# STM32.net
KiCad netlist of a schematic drawn in Altium Designer
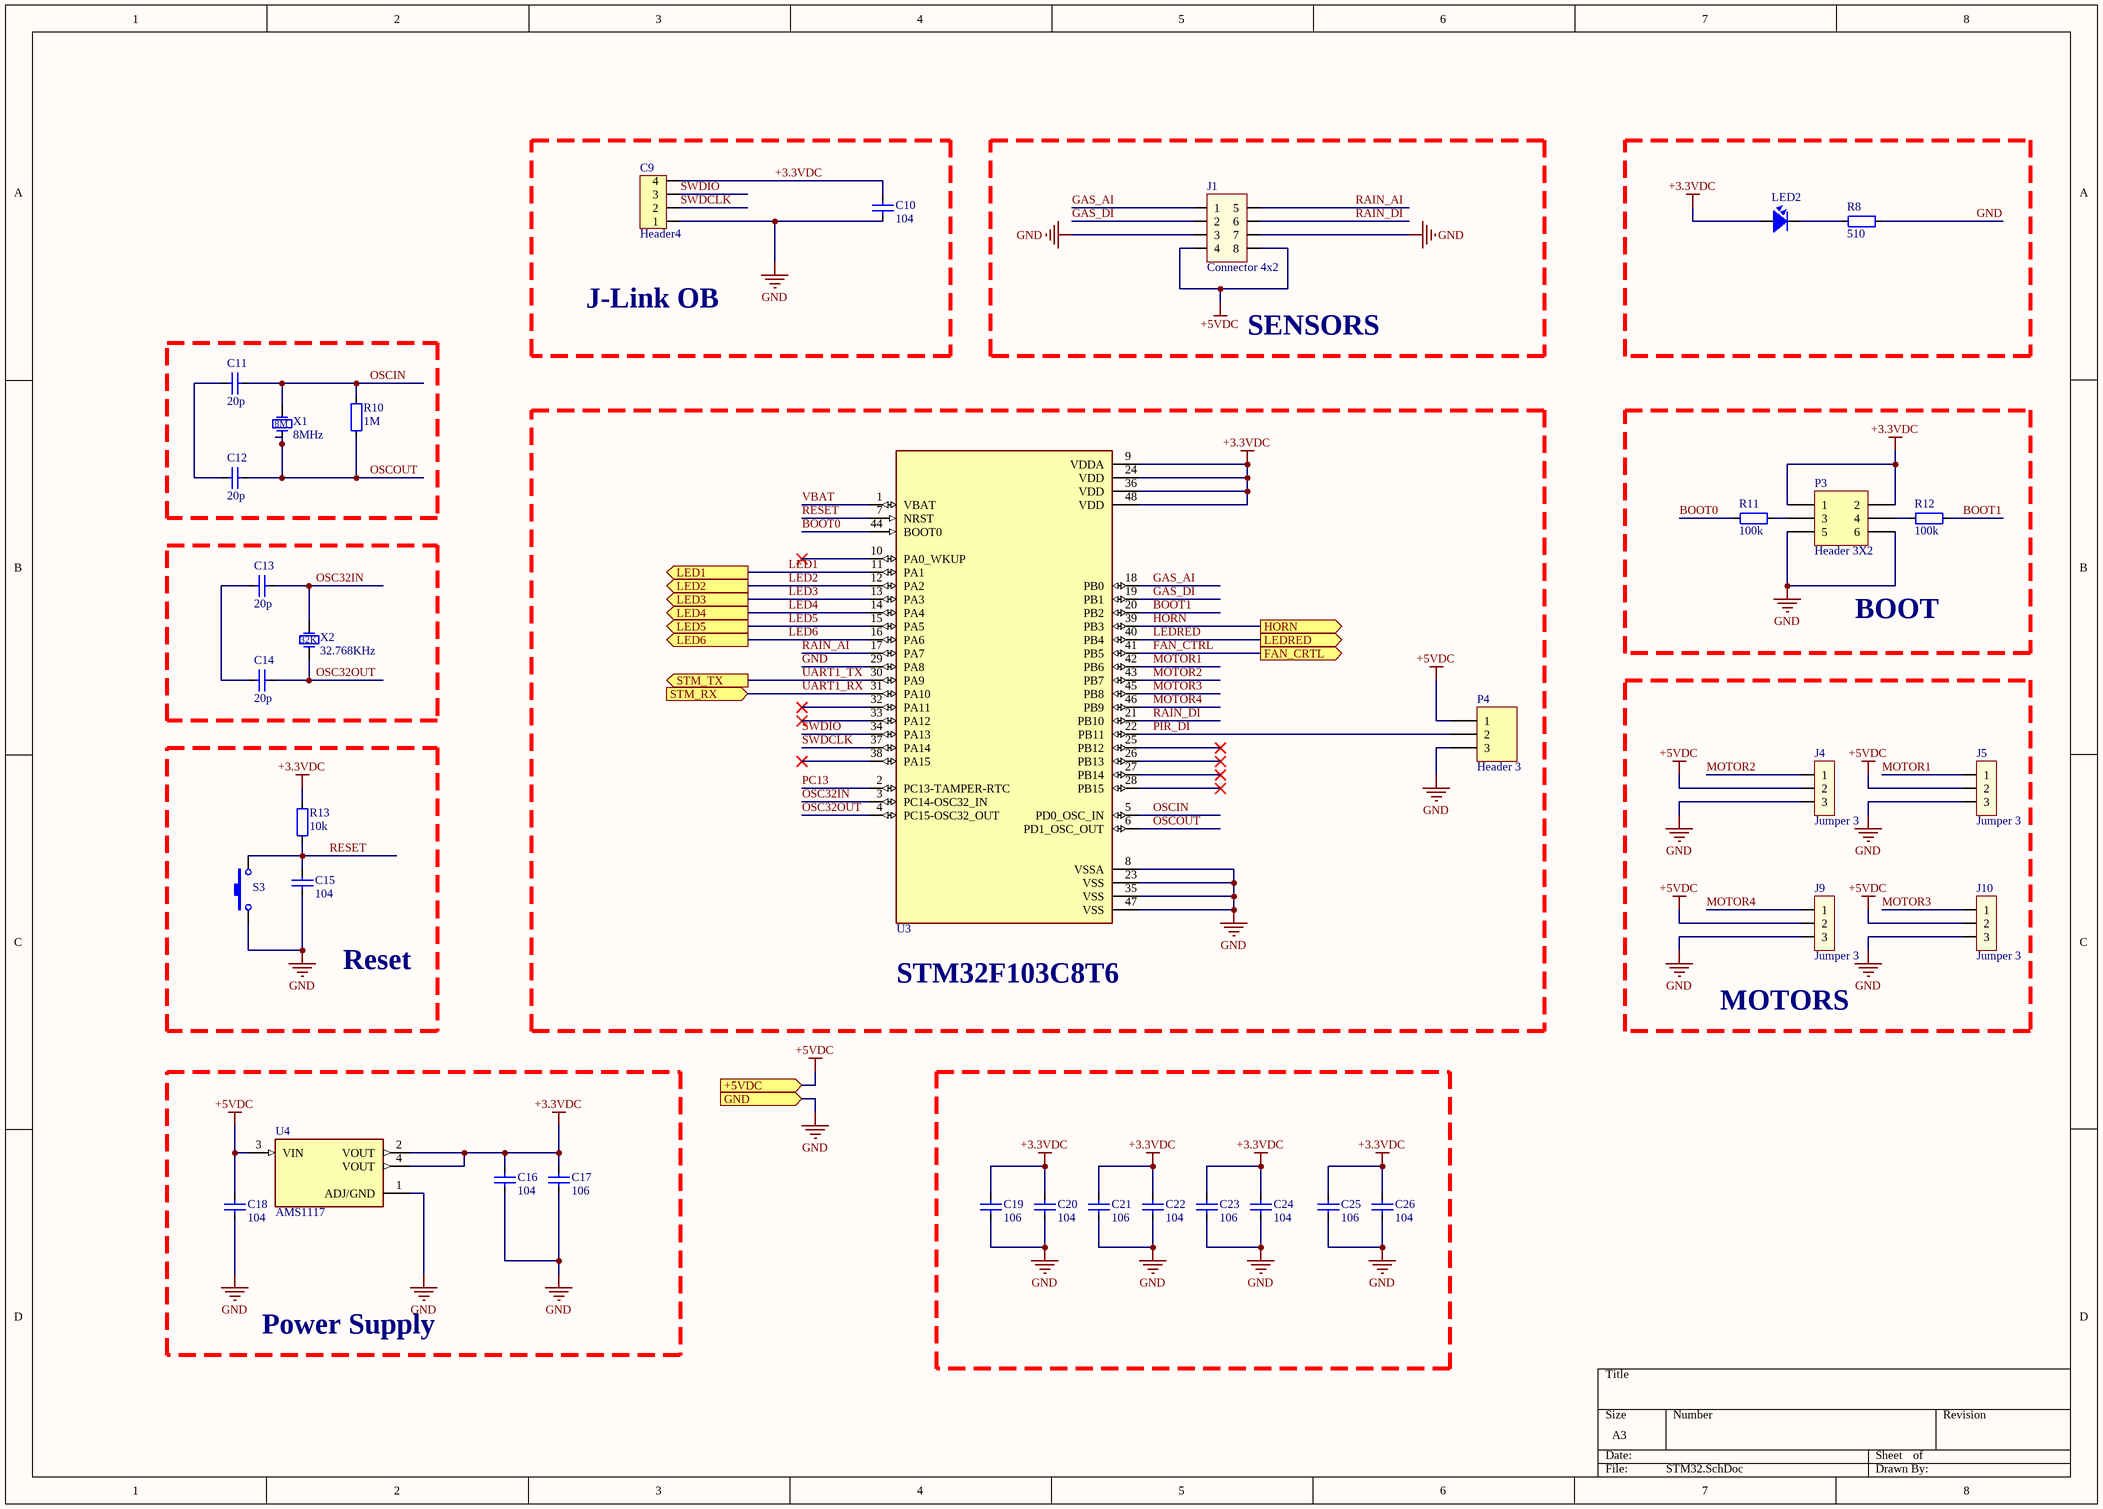
[diagram p0: STM32.SchDoc]

(export (version "E")
  (design (tool "Eeschema 10.0.6"))
  (components
    (comp (ref "C9")
      (value "Header4")
      (footprint "Header4")
      (description "Header IDC, 4 x 1 Pin Vertical 2.54mm Pitch (Non-Boxed, Male)")
      (fields
        (field (name "MANUFACTURER") "Würth Elektronik eiSos GmbH")
        (field (name "PARTNO") "613002143121")
        (field (name "CREATED BY") "Karrer Zheng")
      )
      (libsource (lib "My Library") (part "Header4"))
    )
    (comp (ref "C10")
      (value "104")
      (footprint "CAP_0805")
      (description "Capacitor")
      (fields (field (name "PUBLISHER") "Altium Limited"))
      (libsource (lib "My Library") (part "CapSMD"))
    )
    (comp (ref "C11")
      (value "20p")
      (footprint "CAP_0805")
      (description "Capacitor")
      (fields (field (name "PUBLISHER") "Altium Limited"))
      (libsource (lib "My Library") (part "CapSMD"))
    )
    (comp (ref "C12")
      (value "20p")
      (footprint "CAP_0805")
      (description "Capacitor")
      (fields (field (name "PUBLISHER") "Altium Limited"))
      (libsource (lib "My Library") (part "CapSMD"))
    )
    (comp (ref "C13")
      (value "20p")
      (footprint "CAP_0805")
      (description "Capacitor")
      (fields (field (name "PUBLISHER") "Altium Limited"))
      (libsource (lib "My Library") (part "CapSMD"))
    )
    (comp (ref "C14")
      (value "20p")
      (footprint "CAP_0805")
      (description "Capacitor")
      (fields (field (name "PUBLISHER") "Altium Limited"))
      (libsource (lib "My Library") (part "CapSMD"))
    )
    (comp (ref "C15")
      (value "104")
      (footprint "CAP_0805")
      (description "Capacitor")
      (fields (field (name "PUBLISHER") "Altium Limited"))
      (libsource (lib "My Library") (part "CapSMD"))
    )
    (comp (ref "C16")
      (value "104")
      (footprint "CAP_0805")
      (description "Capacitor")
      (fields (field (name "PUBLISHER") "Altium Limited"))
      (libsource (lib "My Library") (part "CapSMD"))
    )
    (comp (ref "C17")
      (value "106")
      (footprint "CAP_0805")
      (description "Capacitor")
      (fields (field (name "PUBLISHER") "Altium Limited"))
      (libsource (lib "My Library") (part "CapSMD"))
    )
    (comp (ref "C18")
      (value "104")
      (footprint "CAP_0805")
      (description "Capacitor")
      (fields (field (name "PUBLISHER") "Altium Limited"))
      (libsource (lib "My Library") (part "CapSMD"))
    )
    (comp (ref "C19")
      (value "106")
      (footprint "CAP_0805")
      (description "Capacitor")
      (fields (field (name "PUBLISHER") "Altium Limited"))
      (libsource (lib "My Library") (part "CapSMD"))
    )
    (comp (ref "C20")
      (value "104")
      (footprint "CAP_0805")
      (description "Capacitor")
      (fields (field (name "PUBLISHER") "Altium Limited"))
      (libsource (lib "My Library") (part "CapSMD"))
    )
    (comp (ref "C21")
      (value "106")
      (footprint "CAP_0805")
      (description "Capacitor")
      (fields (field (name "PUBLISHER") "Altium Limited"))
      (libsource (lib "My Library") (part "CapSMD"))
    )
    (comp (ref "C22")
      (value "104")
      (footprint "CAP_0805")
      (description "Capacitor")
      (fields (field (name "PUBLISHER") "Altium Limited"))
      (libsource (lib "My Library") (part "CapSMD"))
    )
    (comp (ref "C23")
      (value "106")
      (footprint "CAP_0805")
      (description "Capacitor")
      (fields (field (name "PUBLISHER") "Altium Limited"))
      (libsource (lib "My Library") (part "CapSMD"))
    )
    (comp (ref "C24")
      (value "104")
      (footprint "CAP_0805")
      (description "Capacitor")
      (fields (field (name "PUBLISHER") "Altium Limited"))
      (libsource (lib "My Library") (part "CapSMD"))
    )
    (comp (ref "C25")
      (value "106")
      (footprint "CAP_0805")
      (description "Capacitor")
      (fields (field (name "PUBLISHER") "Altium Limited"))
      (libsource (lib "My Library") (part "CapSMD"))
    )
    (comp (ref "C26")
      (value "104")
      (footprint "CAP_0805")
      (description "Capacitor")
      (fields (field (name "PUBLISHER") "Altium Limited"))
      (libsource (lib "My Library") (part "CapSMD"))
    )
    (comp (ref "J1")
      (value "Connector 4x2")
      (footprint "JP4x2")
      (libsource (lib "My Library") (part "JP4x2"))
    )
    (comp (ref "J4") (value "Jumper 3") (footprint "JP3") (libsource (lib "My Library") (part "JP3")))
    (comp (ref "J5") (value "Jumper 3") (footprint "JP3") (libsource (lib "My Library") (part "JP3")))
    (comp (ref "J9") (value "Jumper 3") (footprint "JP3") (libsource (lib "My Library") (part "JP3")))
    (comp (ref "J10") (value "Jumper 3") (footprint "JP3") (libsource (lib "My Library") (part "JP3")))
    (comp (ref "LED2")
      (value "LED")
      (footprint "LED-0805-Red")
      (description "LED Single colour Green and Red")
      (libsource (lib "My Library") (part "LED"))
    )
    (comp (ref "P3")
      (value "Header 3X2")
      (footprint "HDR2X3")
      (description "Header, 3-Pin, Dual row")
      (fields (field (name "PUBLISHER") "Altium Limited"))
      (libsource (lib "My Library") (part "Header 3X2"))
    )
    (comp (ref "P4")
      (value "Header 3")
      (footprint "HDR1X3")
      (description "Header, 3-Pin")
      (fields (field (name "PUBLISHER") "Altium Limited"))
      (libsource (lib "My Library") (part "Header 3"))
    )
    (comp (ref "R8")
      (value "510")
      (footprint "RES-SMD-0805")
      (description "Resistor")
      (fields
        (field (name "MANUFACTURER") "Generic Components")
        (field (name "PUBLISHER") "Altium Hobart Technology Centre")
      )
      (libsource (lib "My Library") (part "Resistor - SMD"))
    )
    (comp (ref "R10")
      (value "1M")
      (footprint "RES-SMD-0805")
      (description "Resistor")
      (fields
        (field (name "MANUFACTURER") "Generic Components")
        (field (name "PUBLISHER") "Altium Hobart Technology Centre")
      )
      (libsource (lib "My Library") (part "Resistor - SMD"))
    )
    (comp (ref "R11")
      (value "100k")
      (footprint "RES-SMD-0805")
      (description "Resistor")
      (fields
        (field (name "MANUFACTURER") "Generic Components")
        (field (name "PUBLISHER") "Altium Hobart Technology Centre")
      )
      (libsource (lib "My Library") (part "Resistor - SMD"))
    )
    (comp (ref "R12")
      (value "100k")
      (footprint "RES-SMD-0805")
      (description "Resistor")
      (fields
        (field (name "MANUFACTURER") "Generic Components")
        (field (name "PUBLISHER") "Altium Hobart Technology Centre")
      )
      (libsource (lib "My Library") (part "Resistor - SMD"))
    )
    (comp (ref "R13")
      (value "10k")
      (footprint "RES-SMD-0805")
      (description "Resistor")
      (fields
        (field (name "MANUFACTURER") "Generic Components")
        (field (name "PUBLISHER") "Altium Hobart Technology Centre")
      )
      (libsource (lib "My Library") (part "Resistor - SMD"))
    )
    (comp (ref "S3")
      (value "SW-SMD")
      (footprint "SW-SMD")
      (description "Switch")
      (fields (field (name "PUBLISHER") "Altium Limited"))
      (libsource (lib "My Library") (part "SW-SMD"))
    )
    (comp (ref "U3")
      (value "STM32")
      (footprint "LQFP 48")
      (description "STM32 ARM-based 32-bit MCU with 64 Kbytes Flash, 64-pin LQFP, Industrial Temperature")
      (libsource (lib "My Library") (part "STM32F103C8T6"))
    )
    (comp (ref "U4")
      (value "AMS1117")
      (footprint "SOT229P700X180-4N")
      (description "1A LOW DROPOUT VOLTAGE REGULATOR SOT-223")
      (fields (field (name "MF") "Advanced Monolithic Systems"))
      (libsource (lib "AMS1117") (part "AMS1117"))
    )
    (comp (ref "X1")
      (value "8MHz")
      (footprint "CRYSTAL_ABM3 5x3.2mm")
      (description "CRYSTAL 8.0000MHZ 18pF SMD")
      (fields (field (name "MPN") "ABM3-8.000MHZ-D2Y-T"))
      (libsource (lib "BYTECH_HW_LIB_2019") (part "ABM3-8.000MHZ-D2Y-T"))
    )
    (comp (ref "X2")
      (value "32.768KHz")
      (footprint "Crystal_ABS07_SMD-3.2x1.5MM")
      (description "CRYSTAL 32.7680KHZ 12.5pF SMD")
      (fields (field (name "MPN") "ABS07-32.768KHZ-T"))
      (libsource (lib "BYTECH_HW_LIB_2019") (part "ABS07-32.768KHZ-T"))
    )
  )
  (nets
    (net (code "1") (name "+3.3VDC") (class "Default")
      (node (ref "C10") (pin "2") (pinfunction "2_2") (pintype "passive"))
      (node (ref "C16") (pin "2") (pinfunction "2_2") (pintype "passive"))
      (node (ref "C17") (pin "2") (pinfunction "2_2") (pintype "passive"))
      (node (ref "C19") (pin "2") (pinfunction "2_2") (pintype "passive"))
      (node (ref "C20") (pin "2") (pinfunction "2_2") (pintype "passive"))
      (node (ref "C21") (pin "2") (pinfunction "2_2") (pintype "passive"))
      (node (ref "C22") (pin "2") (pinfunction "2_2") (pintype "passive"))
      (node (ref "C23") (pin "2") (pinfunction "2_2") (pintype "passive"))
      (node (ref "C24") (pin "2") (pinfunction "2_2") (pintype "passive"))
      (node (ref "C25") (pin "2") (pinfunction "2_2") (pintype "passive"))
      (node (ref "C26") (pin "2") (pinfunction "2_2") (pintype "passive"))
      (node (ref "C9") (pin "4") (pinfunction "4_4") (pintype "passive"))
      (node (ref "LED2") (pin "1") (pinfunction "1_1") (pintype "passive"))
      (node (ref "P3") (pin "1") (pinfunction "1_1") (pintype "passive"))
      (node (ref "P3") (pin "2") (pinfunction "2_2") (pintype "passive"))
      (node (ref "R13") (pin "2") (pinfunction "2_2") (pintype "passive"))
      (node (ref "U3") (pin "24") (pinfunction "VDD_24") (pintype "power_in"))
      (node (ref "U3") (pin "36") (pinfunction "VDD_36") (pintype "power_in"))
      (node (ref "U3") (pin "48") (pinfunction "VDD_48") (pintype "power_in"))
      (node (ref "U3") (pin "9") (pinfunction "VDDA_9") (pintype "power_in"))
      (node (ref "U4") (pin "2") (pinfunction "VOUT_2") (pintype "output"))
      (node (ref "U4") (pin "4") (pinfunction "VOUT_4") (pintype "output"))
    )
    (net (code "2") (name "+5VDC") (class "Default")
      (node (ref "C18") (pin "2") (pinfunction "2_2") (pintype "passive"))
      (node (ref "J1") (pin "4") (pinfunction "4_4") (pintype "passive"))
      (node (ref "J1") (pin "8") (pinfunction "8_8") (pintype "passive"))
      (node (ref "J10") (pin "2") (pinfunction "2_2") (pintype "passive"))
      (node (ref "J4") (pin "2") (pinfunction "2_2") (pintype "passive"))
      (node (ref "J5") (pin "2") (pinfunction "2_2") (pintype "passive"))
      (node (ref "J9") (pin "2") (pinfunction "2_2") (pintype "passive"))
      (node (ref "P4") (pin "1") (pinfunction "1_1") (pintype "passive"))
      (node (ref "U4") (pin "3") (pinfunction "VIN_3") (pintype "input"))
    )
    (net (code "3") (name "/BOOT0") (class "Default")
      (node (ref "R11") (pin "2") (pinfunction "2_2") (pintype "passive"))
      (node (ref "U3") (pin "44") (pinfunction "BOOT0_44") (pintype "input"))
    )
    (net (code "4") (name "/BOOT1") (class "Default")
      (node (ref "R12") (pin "1") (pinfunction "1_1") (pintype "passive"))
      (node (ref "U3") (pin "20") (pinfunction "PB2_20") (pintype "bidirectional"))
    )
    (net (code "5") (name "/FAN_CTRL") (class "Default")
      (node (ref "U3") (pin "41") (pinfunction "PB5_41") (pintype "bidirectional"))
    )
    (net (code "6") (name "/GAS_AI") (class "Default")
      (node (ref "J1") (pin "1") (pinfunction "1_1") (pintype "passive"))
      (node (ref "U3") (pin "18") (pinfunction "PB0_18") (pintype "bidirectional"))
    )
    (net (code "7") (name "/GAS_DI") (class "Default")
      (node (ref "J1") (pin "2") (pinfunction "2_2") (pintype "passive"))
      (node (ref "U3") (pin "19") (pinfunction "PB1_19") (pintype "bidirectional"))
    )
    (net (code "8") (name "/HORN") (class "Default")
      (node (ref "U3") (pin "39") (pinfunction "PB3_39") (pintype "bidirectional"))
    )
    (net (code "9") (name "/LED1") (class "Default")
      (node (ref "U3") (pin "11") (pinfunction "PA1_11") (pintype "bidirectional"))
    )
    (net (code "10") (name "/LED2") (class "Default")
      (node (ref "U3") (pin "12") (pinfunction "PA2_12") (pintype "bidirectional"))
    )
    (net (code "11") (name "/LED3") (class "Default")
      (node (ref "U3") (pin "13") (pinfunction "PA3_13") (pintype "bidirectional"))
    )
    (net (code "12") (name "/LED4") (class "Default")
      (node (ref "U3") (pin "14") (pinfunction "PA4_14") (pintype "bidirectional"))
    )
    (net (code "13") (name "/LED5") (class "Default")
      (node (ref "U3") (pin "15") (pinfunction "PA5_15") (pintype "bidirectional"))
    )
    (net (code "14") (name "/LED6") (class "Default")
      (node (ref "U3") (pin "16") (pinfunction "PA6_16") (pintype "bidirectional"))
    )
    (net (code "15") (name "/LEDRED") (class "Default")
      (node (ref "U3") (pin "40") (pinfunction "PB4_40") (pintype "bidirectional"))
    )
    (net (code "16") (name "/MOTOR1") (class "Default")
      (node (ref "J5") (pin "1") (pinfunction "1_1") (pintype "passive"))
      (node (ref "U3") (pin "42") (pinfunction "PB6_42") (pintype "bidirectional"))
    )
    (net (code "17") (name "/MOTOR2") (class "Default")
      (node (ref "J4") (pin "1") (pinfunction "1_1") (pintype "passive"))
      (node (ref "U3") (pin "43") (pinfunction "PB7_43") (pintype "bidirectional"))
    )
    (net (code "18") (name "/MOTOR3") (class "Default")
      (node (ref "J10") (pin "1") (pinfunction "1_1") (pintype "passive"))
      (node (ref "U3") (pin "45") (pinfunction "PB8_45") (pintype "bidirectional"))
    )
    (net (code "19") (name "/MOTOR4") (class "Default")
      (node (ref "J9") (pin "1") (pinfunction "1_1") (pintype "passive"))
      (node (ref "U3") (pin "46") (pinfunction "PB9_46") (pintype "bidirectional"))
    )
    (net (code "20") (name "/OSC32IN") (class "Default")
      (node (ref "C13") (pin "1") (pinfunction "1_1") (pintype "passive"))
      (node (ref "U3") (pin "3") (pinfunction "PC14-OSC32_IN_3") (pintype "bidirectional"))
      (node (ref "X2") (pin "1") (pinfunction "OSC1_1") (pintype "passive"))
    )
    (net (code "21") (name "/OSC32OUT") (class "Default")
      (node (ref "C14") (pin "1") (pinfunction "1_1") (pintype "passive"))
      (node (ref "U3") (pin "4") (pinfunction "PC15-OSC32_OUT_4") (pintype "bidirectional"))
      (node (ref "X2") (pin "2") (pinfunction "OSC2_2") (pintype "passive"))
    )
    (net (code "22") (name "/OSCIN") (class "Default")
      (node (ref "C11") (pin "1") (pinfunction "1_1") (pintype "passive"))
      (node (ref "R10") (pin "2") (pinfunction "2_2") (pintype "passive"))
      (node (ref "U3") (pin "5") (pinfunction "PD0_OSC_IN_5") (pintype "bidirectional"))
      (node (ref "X1") (pin "1") (pinfunction "OSC1_1") (pintype "passive"))
    )
    (net (code "23") (name "/OSCOUT") (class "Default")
      (node (ref "C12") (pin "1") (pinfunction "1_1") (pintype "passive"))
      (node (ref "R10") (pin "1") (pinfunction "1_1") (pintype "passive"))
      (node (ref "U3") (pin "6") (pinfunction "PD1_OSC_OUT_6") (pintype "bidirectional"))
      (node (ref "X1") (pin "2") (pinfunction "OSC2_2") (pintype "passive"))
    )
    (net (code "24") (name "/PC13") (class "Default")
      (node (ref "U3") (pin "2") (pinfunction "PC13-TAMPER-RTC_2") (pintype "bidirectional"))
    )
    (net (code "25") (name "/PIR_DI") (class "Default")
      (node (ref "P4") (pin "2") (pinfunction "2_2") (pintype "passive"))
      (node (ref "U3") (pin "22") (pinfunction "PB11_22") (pintype "bidirectional"))
    )
    (net (code "26") (name "/RAIN_AI") (class "Default")
      (node (ref "J1") (pin "5") (pinfunction "5_5") (pintype "passive"))
      (node (ref "U3") (pin "17") (pinfunction "PA7_17") (pintype "bidirectional"))
    )
    (net (code "27") (name "/RAIN_DI") (class "Default")
      (node (ref "J1") (pin "6") (pinfunction "6_6") (pintype "passive"))
      (node (ref "U3") (pin "21") (pinfunction "PB10_21") (pintype "bidirectional"))
    )
    (net (code "28") (name "/RESET") (class "Default")
      (node (ref "C15") (pin "2") (pinfunction "2_2") (pintype "passive"))
      (node (ref "R13") (pin "1") (pinfunction "1_1") (pintype "passive"))
      (node (ref "S3") (pin "2") (pinfunction "2_2") (pintype "passive"))
      (node (ref "U3") (pin "7") (pinfunction "NRST_7") (pintype "input"))
    )
    (net (code "29") (name "/SWDCLK") (class "Default")
      (node (ref "C9") (pin "2") (pinfunction "2_2") (pintype "passive"))
      (node (ref "U3") (pin "37") (pinfunction "PA14_37") (pintype "bidirectional"))
    )
    (net (code "30") (name "/SWDIO") (class "Default")
      (node (ref "C9") (pin "3") (pinfunction "3_3") (pintype "passive"))
      (node (ref "U3") (pin "34") (pinfunction "PA13_34") (pintype "bidirectional"))
    )
    (net (code "31") (name "/UART1_RX") (class "Default")
      (node (ref "U3") (pin "31") (pinfunction "PA10_31") (pintype "bidirectional"))
    )
    (net (code "32") (name "/UART1_TX") (class "Default")
      (node (ref "U3") (pin "30") (pinfunction "PA9_30") (pintype "bidirectional"))
    )
    (net (code "33") (name "/VBAT") (class "Default")
      (node (ref "U3") (pin "1") (pinfunction "VBAT_1") (pintype "bidirectional"))
    )
    (net (code "34") (name "GND") (class "Default")
      (node (ref "C10") (pin "1") (pinfunction "1_1") (pintype "passive"))
      (node (ref "C15") (pin "1") (pinfunction "1_1") (pintype "passive"))
      (node (ref "C16") (pin "1") (pinfunction "1_1") (pintype "passive"))
      (node (ref "C17") (pin "1") (pinfunction "1_1") (pintype "passive"))
      (node (ref "C18") (pin "1") (pinfunction "1_1") (pintype "passive"))
      (node (ref "C19") (pin "1") (pinfunction "1_1") (pintype "passive"))
      (node (ref "C20") (pin "1") (pinfunction "1_1") (pintype "passive"))
      (node (ref "C21") (pin "1") (pinfunction "1_1") (pintype "passive"))
      (node (ref "C22") (pin "1") (pinfunction "1_1") (pintype "passive"))
      (node (ref "C23") (pin "1") (pinfunction "1_1") (pintype "passive"))
      (node (ref "C24") (pin "1") (pinfunction "1_1") (pintype "passive"))
      (node (ref "C25") (pin "1") (pinfunction "1_1") (pintype "passive"))
      (node (ref "C26") (pin "1") (pinfunction "1_1") (pintype "passive"))
      (node (ref "C9") (pin "1") (pinfunction "1_1") (pintype "passive"))
      (node (ref "J1") (pin "3") (pinfunction "3_3") (pintype "passive"))
      (node (ref "J1") (pin "7") (pinfunction "7_7") (pintype "passive"))
      (node (ref "J10") (pin "3") (pinfunction "3_3") (pintype "passive"))
      (node (ref "J4") (pin "3") (pinfunction "3_3") (pintype "passive"))
      (node (ref "J5") (pin "3") (pinfunction "3_3") (pintype "passive"))
      (node (ref "J9") (pin "3") (pinfunction "3_3") (pintype "passive"))
      (node (ref "P3") (pin "5") (pinfunction "5_5") (pintype "passive"))
      (node (ref "P3") (pin "6") (pinfunction "6_6") (pintype "passive"))
      (node (ref "P4") (pin "3") (pinfunction "3_3") (pintype "passive"))
      (node (ref "R8") (pin "1") (pinfunction "1_1") (pintype "passive"))
      (node (ref "S3") (pin "1") (pinfunction "1_1") (pintype "passive"))
      (node (ref "U3") (pin "23") (pinfunction "VSS_23") (pintype "power_in"))
      (node (ref "U3") (pin "29") (pinfunction "PA8_29") (pintype "bidirectional"))
      (node (ref "U3") (pin "35") (pinfunction "VSS_35") (pintype "power_in"))
      (node (ref "U3") (pin "47") (pinfunction "VSS_47") (pintype "power_in"))
      (node (ref "U3") (pin "8") (pinfunction "VSSA_8") (pintype "power_in"))
      (node (ref "U4") (pin "1") (pinfunction "ADJ/GND_1") (pintype "power_in"))
    )
    (net (code "35") (name "Net-(C11-Pad2)") (class "Default")
      (node (ref "C11") (pin "2") (pinfunction "2_2") (pintype "passive"))
      (node (ref "C12") (pin "2") (pinfunction "2_2") (pintype "passive"))
    )
    (net (code "36") (name "Net-(C13-Pad2)") (class "Default")
      (node (ref "C13") (pin "2") (pinfunction "2_2") (pintype "passive"))
      (node (ref "C14") (pin "2") (pinfunction "2_2") (pintype "passive"))
    )
    (net (code "37") (name "Net-(LED2-Pad2)") (class "Default")
      (node (ref "LED2") (pin "2") (pinfunction "2_2") (pintype "passive"))
      (node (ref "R8") (pin "2") (pinfunction "2_2") (pintype "passive"))
    )
    (net (code "38") (name "Net-(P3-Pad3)") (class "Default")
      (node (ref "P3") (pin "3") (pinfunction "3_3") (pintype "passive"))
      (node (ref "R11") (pin "1") (pinfunction "1_1") (pintype "passive"))
    )
    (net (code "39") (name "Net-(P3-Pad4)") (class "Default")
      (node (ref "P3") (pin "4") (pinfunction "4_4") (pintype "passive"))
      (node (ref "R12") (pin "2") (pinfunction "2_2") (pintype "passive"))
    )
    (net (code "40") (name "unconnected-(U3-PA0_WKUP-Pad10)") (class "Default")
      (node (ref "U3") (pin "10") (pinfunction "PA0_WKUP_10") (pintype "bidirectional+no_connect"))
    )
    (net (code "41") (name "unconnected-(U3-PA11-Pad32)") (class "Default")
      (node (ref "U3") (pin "32") (pinfunction "PA11_32") (pintype "bidirectional+no_connect"))
    )
    (net (code "42") (name "unconnected-(U3-PA12-Pad33)") (class "Default")
      (node (ref "U3") (pin "33") (pinfunction "PA12_33") (pintype "bidirectional+no_connect"))
    )
    (net (code "43") (name "unconnected-(U3-PA15-Pad38)") (class "Default")
      (node (ref "U3") (pin "38") (pinfunction "PA15_38") (pintype "bidirectional+no_connect"))
    )
    (net (code "44") (name "unconnected-(U3-PB12-Pad25)") (class "Default")
      (node (ref "U3") (pin "25") (pinfunction "PB12_25") (pintype "bidirectional+no_connect"))
    )
    (net (code "45") (name "unconnected-(U3-PB13-Pad26)") (class "Default")
      (node (ref "U3") (pin "26") (pinfunction "PB13_26") (pintype "bidirectional+no_connect"))
    )
    (net (code "46") (name "unconnected-(U3-PB14-Pad27)") (class "Default")
      (node (ref "U3") (pin "27") (pinfunction "PB14_27") (pintype "bidirectional+no_connect"))
    )
    (net (code "47") (name "unconnected-(U3-PB15-Pad28)") (class "Default")
      (node (ref "U3") (pin "28") (pinfunction "PB15_28") (pintype "bidirectional+no_connect"))
    )
  )
)
